# rel-clock.net
KiCad netlist of a schematic drawn in EAGLE
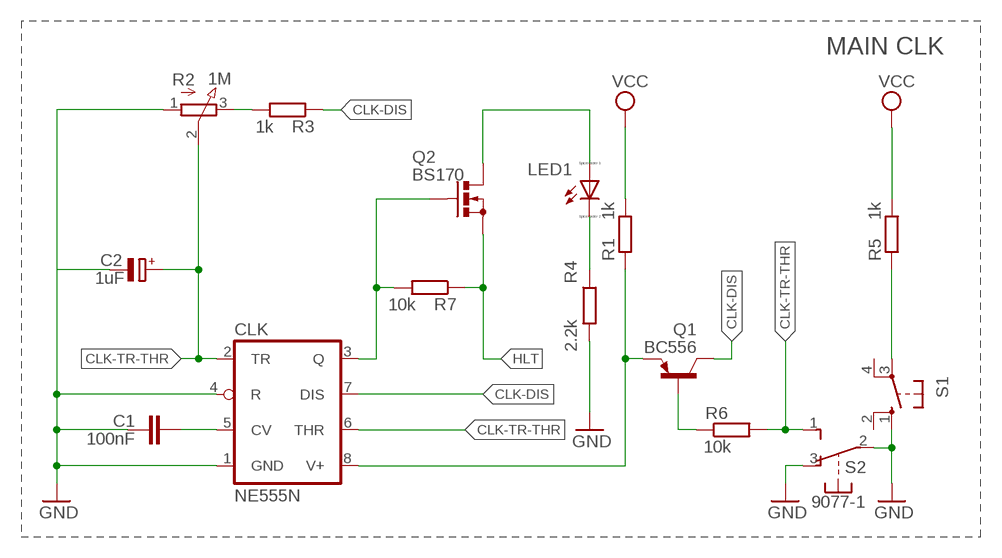
[diagram p0: schematic, sheet 1]

(export (version "E")
  (design (tool "Eeschema 10.0.6"))
  (components
    (comp (ref "C1")
      (value "100nF")
      (footprint "eagle-import:C025-050X050")
      (libsource (lib "eagle-import") (part "C-EU025-050X050"))
    )
    (comp (ref "C2")
      (value "1uF")
      (footprint "eagle-import:E2-5")
      (libsource (lib "eagle-import") (part "CPOL-EUE2-5"))
    )
    (comp (ref "CLK")
      (value "NE555N")
      (footprint "eagle-import:DIL08")
      (libsource (lib "eagle-import") (part "555NNE"))
    )
    (comp (ref "LED1")
      (value "LED_ELD260")
      (footprint "eagle-import:LED_LD260")
      (libsource (lib "eagle-import") (part "LED_ELD260"))
    )
    (comp (ref "Q1")
      (value "BC556")
      (footprint "eagle-import:TO92-EBC")
      (libsource (lib "eagle-import") (part "BC556"))
    )
    (comp (ref "Q2")
      (value "BS170")
      (footprint "eagle-import:SOT54E")
      (libsource (lib "eagle-import") (part "BS170"))
    )
    (comp (ref "R1")
      (value "1k")
      (footprint "eagle-import:0204_5")
      (libsource (lib "eagle-import") (part "R-EU_0204/5"))
    )
    (comp (ref "R2")
      (value "1M")
      (footprint "eagle-import:3RP_1610N")
      (libsource (lib "eagle-import") (part "3RP/1610N"))
    )
    (comp (ref "R3")
      (value "1k")
      (footprint "eagle-import:0204_5")
      (libsource (lib "eagle-import") (part "R-EU_0204/5"))
    )
    (comp (ref "R4")
      (value "2.2k")
      (footprint "eagle-import:0204_5")
      (libsource (lib "eagle-import") (part "R-EU_0204/5"))
    )
    (comp (ref "R5")
      (value "1k")
      (footprint "eagle-import:0204_5")
      (libsource (lib "eagle-import") (part "R-EU_0204/5"))
    )
    (comp (ref "R6")
      (value "10k")
      (footprint "eagle-import:0204_5")
      (libsource (lib "eagle-import") (part "R-EU_0204/5"))
    )
    (comp (ref "R7")
      (value "10k")
      (footprint "eagle-import:0204_5")
      (libsource (lib "eagle-import") (part "R-EU_0204/5"))
    )
    (comp (ref "S1")
      (value "10-XX")
      (footprint "eagle-import:B3F-10XX")
      (fields (field (name "MPN") "B3F-1000"))
      (libsource (lib "eagle-import") (part "10-XX"))
    )
    (comp (ref "S2")
      (value "9077-1")
      (footprint "eagle-import:9077-1")
      (libsource (lib "eagle-import") (part "9077-1"))
    )
  )
  (nets
    (net (code "1") (name "CLK-DIS") (class "Default")
      (node (ref "CLK") (pin "7") (pinfunction "DIS_7") (pintype "input"))
      (node (ref "Q1") (pin "C") (pinfunction "C_C") (pintype "passive"))
      (node (ref "R3") (pin "1") (pinfunction "1_1") (pintype "passive"))
    )
    (net (code "2") (name "CLK-TR-THR") (class "Default")
      (node (ref "C2") (pin "+") (pinfunction "+_+") (pintype "passive"))
      (node (ref "CLK") (pin "2") (pinfunction "TR_2") (pintype "input"))
      (node (ref "CLK") (pin "6") (pinfunction "THR_6") (pintype "input"))
      (node (ref "Q1") (pin "B") (pinfunction "B_B") (pintype "passive"))
      (node (ref "R2") (pin "2") (pinfunction "S_2") (pintype "passive"))
      (node (ref "R6") (pin "1") (pinfunction "1_1") (pintype "passive"))
      (node (ref "R6") (pin "2") (pinfunction "2_2") (pintype "passive"))
      (node (ref "S2") (pin "1") (pinfunction "S_1") (pintype "passive"))
    )
    (net (code "3") (name "GND") (class "Default")
      (node (ref "C1") (pin "1") (pinfunction "1_1") (pintype "passive"))
      (node (ref "C2") (pin "-") (pinfunction "-_-") (pintype "passive"))
      (node (ref "CLK") (pin "1") (pinfunction "GND_1") (pintype "power_in"))
      (node (ref "CLK") (pin "4") (pinfunction "R_4") (pintype "input"))
      (node (ref "R2") (pin "1") (pinfunction "A_1") (pintype "passive"))
      (node (ref "R4") (pin "2") (pinfunction "2_2") (pintype "passive"))
      (node (ref "S1") (pin "1") (pinfunction "S_1") (pintype "passive"))
      (node (ref "S2") (pin "2") (pinfunction "P_2") (pintype "passive"))
      (node (ref "S2") (pin "3") (pinfunction "O_3") (pintype "passive"))
    )
    (net (code "4") (name "HLT") (class "Default")
      (node (ref "Q2") (pin "S") (pinfunction "S_S") (pintype "passive"))
      (node (ref "R7") (pin "1") (pinfunction "1_1") (pintype "passive"))
    )
    (net (code "5") (name "Net-(CLK-CV)") (class "Default")
      (node (ref "C1") (pin "2") (pinfunction "2_2") (pintype "passive"))
      (node (ref "CLK") (pin "5") (pinfunction "CV_5") (pintype "input"))
    )
    (net (code "6") (name "Net-(CLK-Q)") (class "Default")
      (node (ref "CLK") (pin "3") (pinfunction "Q_3") (pintype "output"))
      (node (ref "Q2") (pin "G") (pinfunction "G_G") (pintype "passive"))
      (node (ref "R7") (pin "2") (pinfunction "2_2") (pintype "passive"))
    )
    (net (code "7") (name "Net-(CLK-V+)") (class "Default")
      (node (ref "CLK") (pin "8") (pinfunction "V+_8") (pintype "power_in"))
      (node (ref "Q1") (pin "E") (pinfunction "E_E") (pintype "passive"))
      (node (ref "R1") (pin "1") (pinfunction "1_1") (pintype "passive"))
    )
    (net (code "8") (name "Net-(LED1-C)") (class "Default")
      (node (ref "LED1") (pin "K") (pinfunction "C_K") (pintype "passive"))
      (node (ref "R4") (pin "1") (pinfunction "1_1") (pintype "passive"))
    )
    (net (code "9") (name "Net-(LED1-PadA)") (class "Default")
      (node (ref "LED1") (pin "A") (pinfunction "A_A") (pintype "passive"))
      (node (ref "Q2") (pin "D") (pinfunction "D_D") (pintype "passive"))
    )
    (net (code "10") (name "Net-(R2-E)") (class "Default")
      (node (ref "R2") (pin "3") (pinfunction "E_3") (pintype "passive"))
      (node (ref "R3") (pin "2") (pinfunction "2_2") (pintype "passive"))
    )
    (net (code "11") (name "Net-(S1-P)") (class "Default")
      (node (ref "R5") (pin "1") (pinfunction "1_1") (pintype "passive"))
      (node (ref "S1") (pin "3") (pinfunction "P_3") (pintype "passive"))
    )
    (net (code "12") (name "VCC") (class "Default")
      (node (ref "R1") (pin "2") (pinfunction "2_2") (pintype "passive"))
      (node (ref "R5") (pin "2") (pinfunction "2_2") (pintype "passive"))
    )
    (net (code "13") (name "unconnected-(S1-P1-Pad4)") (class "Default")
      (node (ref "S1") (pin "4") (pinfunction "P1_4") (pintype "passive"))
    )
    (net (code "14") (name "unconnected-(S1-S1-Pad2)") (class "Default")
      (node (ref "S1") (pin "2") (pinfunction "S1_2") (pintype "passive"))
    )
  )
)
